# mcu.net
KiCad netlist of a schematic drawn in Altium Designer
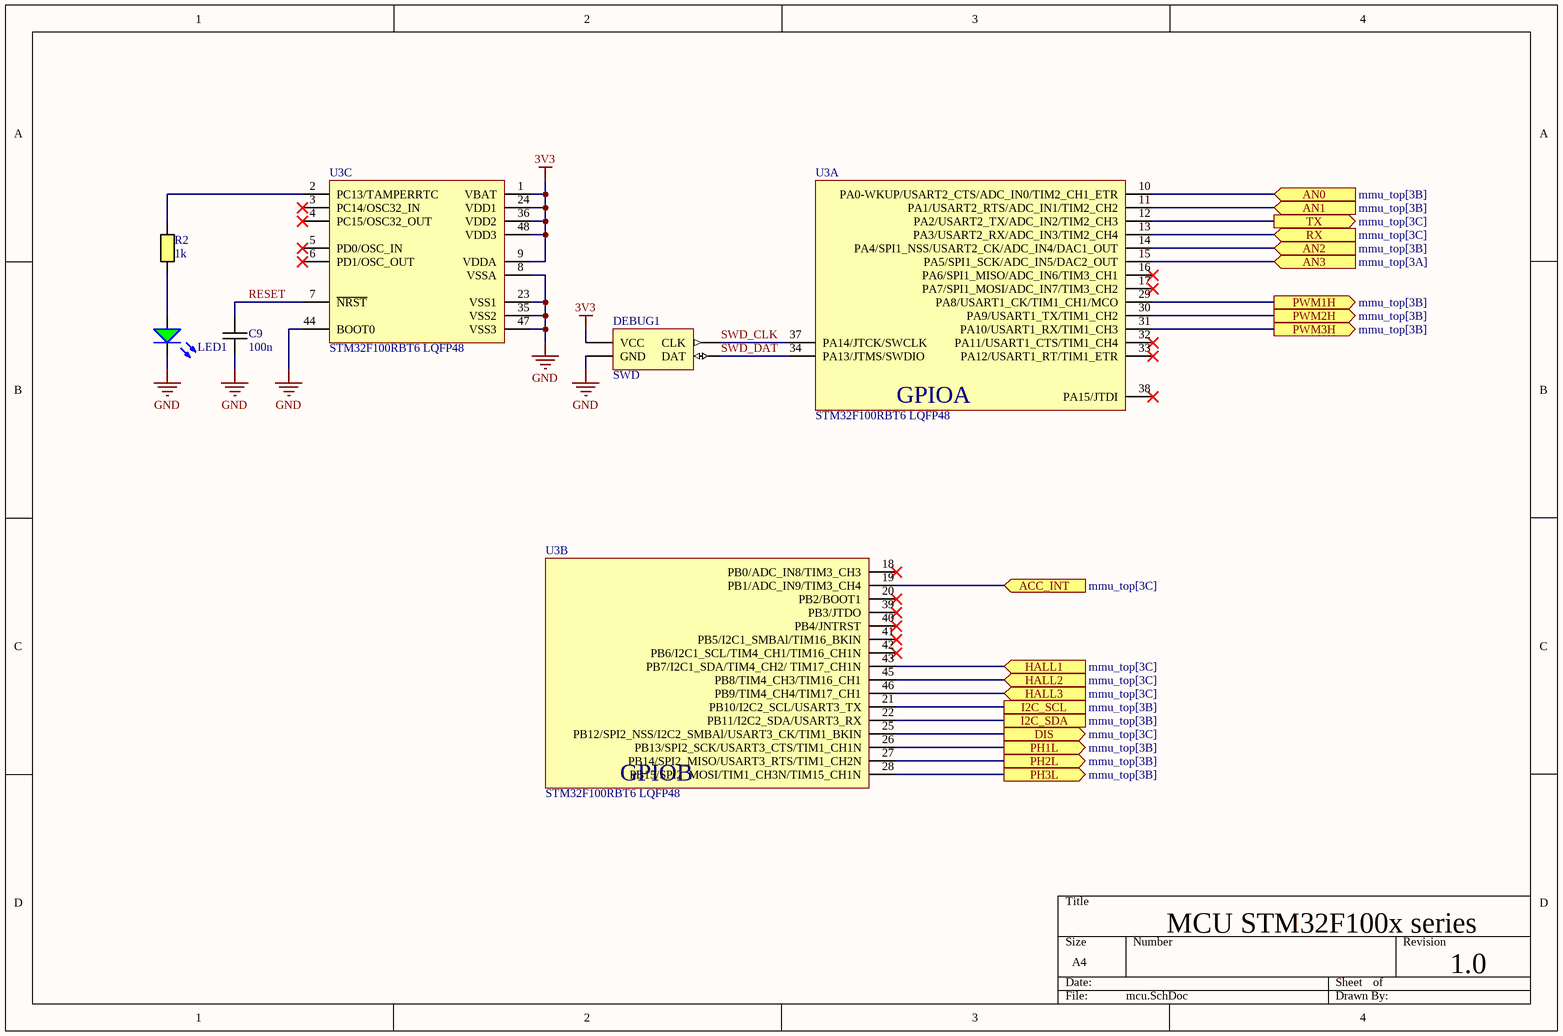
[diagram p0: mcu.SchDoc]

(export (version "E")
  (design (tool "Eeschema 10.0.6"))
  (components
    (comp (ref "C9")
      (value "100n")
      (footprint "CAPC0603(1608)55_N")
      (description "Ceramic capacitor Medium density")
      (libsource (lib "Discrete") (part "Capacitor M"))
    )
    (comp (ref "DEBUG1")
      (value "SWD")
      (footprint "PIN HEADER SINGLE 4")
      (description "SWD ST DEBUG")
      (libsource (lib "Debug") (part "SWD DEBUG"))
    )
    (comp (ref "LED1")
      (value "1206 LED GREEN")
      (footprint "1206 LED GREEN")
      (libsource (lib "Optical") (part "1206 LED GREEN"))
    )
    (comp (ref "R2")
      (value "1k")
      (footprint "RESC0603(1608)_N")
      (description "Resistor Medium Density")
      (libsource (lib "Discrete") (part "Resistor M"))
    )
    (comp (ref "U3")
      (value "STM32F100RBT6 LQFP48")
      (footprint "LQFP48")
      (libsource (lib "Microcontrollers") (part "STM32F100RBT6 LQFP48"))
    )
  )
  (nets
    (net (code "1") (name "/ACC_INT") (class "Default")
      (node (ref "U3") (pin "19") (pinfunction "PB1/ADC_IN9/TIM3_CH4_19") (pintype "passive"))
    )
    (net (code "2") (name "/AN0") (class "Default")
      (node (ref "U3") (pin "10") (pinfunction "PA0-WKUP/USART2_CTS/ADC_IN0/TIM2_CH1_ETR_10") (pintype "passive"))
    )
    (net (code "3") (name "/AN1") (class "Default")
      (node (ref "U3") (pin "11") (pinfunction "PA1/USART2_RTS/ADC_IN1/TIM2_CH2_11") (pintype "passive"))
    )
    (net (code "4") (name "/AN2") (class "Default")
      (node (ref "U3") (pin "14") (pinfunction "PA4/SPI1_NSS/USART2_CK/ADC_IN4/DAC1_OUT_14") (pintype "passive"))
    )
    (net (code "5") (name "/AN3") (class "Default")
      (node (ref "U3") (pin "15") (pinfunction "PA5/SPI1_SCK/ADC_IN5/DAC2_OUT_15") (pintype "passive"))
    )
    (net (code "6") (name "/DIS") (class "Default")
      (node (ref "U3") (pin "25") (pinfunction "PB12/SPI2_NSS/I2C2_SMBAl/USART3_CK/TIM1_BKIN_25") (pintype "passive"))
    )
    (net (code "7") (name "/HALL1") (class "Default")
      (node (ref "U3") (pin "43") (pinfunction "PB7/I2C1_SDA/TIM4_CH2/_TIM17_CH1N_43") (pintype "passive"))
    )
    (net (code "8") (name "/HALL2") (class "Default")
      (node (ref "U3") (pin "45") (pinfunction "PB8/TIM4_CH3/TIM16_CH1_45") (pintype "passive"))
    )
    (net (code "9") (name "/HALL3") (class "Default")
      (node (ref "U3") (pin "46") (pinfunction "PB9/TIM4_CH4/TIM17_CH1_46") (pintype "passive"))
    )
    (net (code "10") (name "/I2C_SCL") (class "Default")
      (node (ref "U3") (pin "21") (pinfunction "PB10/I2C2_SCL/USART3_TX_21") (pintype "passive"))
    )
    (net (code "11") (name "/I2C_SDA") (class "Default")
      (node (ref "U3") (pin "22") (pinfunction "PB11/I2C2_SDA/USART3_RX_22") (pintype "passive"))
    )
    (net (code "12") (name "/PH1L") (class "Default")
      (node (ref "U3") (pin "26") (pinfunction "PB13/SPI2_SCK/USART3_CTS/TIM1_CH1N_26") (pintype "passive"))
    )
    (net (code "13") (name "/PH2L") (class "Default")
      (node (ref "U3") (pin "27") (pinfunction "PB14/SPI2_MISO/USART3_RTS/TIM1_CH2N_27") (pintype "passive"))
    )
    (net (code "14") (name "/PH3L") (class "Default")
      (node (ref "U3") (pin "28") (pinfunction "PB15/SPI2_MOSI/TIM1_CH3N/TIM15_CH1N_28") (pintype "passive"))
    )
    (net (code "15") (name "/PWM1H") (class "Default")
      (node (ref "U3") (pin "29") (pinfunction "PA8/USART1_CK/TIM1_CH1/MCO_29") (pintype "passive"))
    )
    (net (code "16") (name "/PWM2H") (class "Default")
      (node (ref "U3") (pin "30") (pinfunction "PA9/USART1_TX/TIM1_CH2_30") (pintype "passive"))
    )
    (net (code "17") (name "/PWM3H") (class "Default")
      (node (ref "U3") (pin "31") (pinfunction "PA10/USART1_RX/TIM1_CH3_31") (pintype "passive"))
    )
    (net (code "18") (name "/RESET") (class "Default")
      (node (ref "C9") (pin "1") (pinfunction "1_1") (pintype "passive"))
      (node (ref "U3") (pin "7") (pinfunction "~{NRST}_7") (pintype "passive"))
    )
    (net (code "19") (name "/RX") (class "Default")
      (node (ref "U3") (pin "13") (pinfunction "PA3/USART2_RX/ADC_IN3/TIM2_CH4_13") (pintype "passive"))
    )
    (net (code "20") (name "/SWD_CLK") (class "Default")
      (node (ref "DEBUG1") (pin "2") (pinfunction "CLK_2") (pintype "output"))
      (node (ref "U3") (pin "37") (pinfunction "PA14/JTCK/SWCLK_37") (pintype "passive"))
    )
    (net (code "21") (name "/SWD_DAT") (class "Default")
      (node (ref "DEBUG1") (pin "4") (pinfunction "DAT_4") (pintype "bidirectional"))
      (node (ref "U3") (pin "34") (pinfunction "PA13/JTMS/SWDIO_34") (pintype "passive"))
    )
    (net (code "22") (name "/TX") (class "Default")
      (node (ref "U3") (pin "12") (pinfunction "PA2/USART2_TX/ADC_IN2/TIM2_CH3_12") (pintype "passive"))
    )
    (net (code "23") (name "3V3") (class "Default")
      (node (ref "DEBUG1") (pin "1") (pinfunction "VCC_1") (pintype "power_in"))
      (node (ref "U3") (pin "1") (pinfunction "VBAT_1") (pintype "passive"))
      (node (ref "U3") (pin "24") (pinfunction "VDD1_24") (pintype "power_in"))
      (node (ref "U3") (pin "36") (pinfunction "VDD2_36") (pintype "power_in"))
      (node (ref "U3") (pin "48") (pinfunction "VDD3_48") (pintype "power_in"))
      (node (ref "U3") (pin "9") (pinfunction "VDDA_9") (pintype "power_in"))
    )
    (net (code "24") (name "GND") (class "Default")
      (node (ref "C9") (pin "2") (pinfunction "2_2") (pintype "passive"))
      (node (ref "DEBUG1") (pin "3") (pinfunction "GND_3") (pintype "power_in"))
      (node (ref "LED1") (pin "K") (pinfunction "K_K") (pintype "passive"))
      (node (ref "U3") (pin "23") (pinfunction "VSS1_23") (pintype "power_in"))
      (node (ref "U3") (pin "35") (pinfunction "VSS2_35") (pintype "power_in"))
      (node (ref "U3") (pin "44") (pinfunction "BOOT0_44") (pintype "passive"))
      (node (ref "U3") (pin "47") (pinfunction "VSS3_47") (pintype "power_in"))
      (node (ref "U3") (pin "8") (pinfunction "VSSA_8") (pintype "power_in"))
    )
    (net (code "25") (name "Net-(LED1-PadA)") (class "Default")
      (node (ref "LED1") (pin "A") (pinfunction "A_A") (pintype "passive"))
      (node (ref "R2") (pin "1") (pinfunction "1_1") (pintype "passive"))
    )
    (net (code "26") (name "Net-(U3C-PC13{slash}TAMPERRTC)") (class "Default")
      (node (ref "R2") (pin "2") (pinfunction "2_2") (pintype "passive"))
      (node (ref "U3") (pin "2") (pinfunction "PC13/TAMPERRTC_2") (pintype "passive"))
    )
    (net (code "27") (name "unconnected-(U3A-PA6{slash}SPI1_MISO{slash}ADC_IN6{slash}TIM3_CH1-Pad16)") (class "Default")
      (node (ref "U3") (pin "16") (pinfunction "PA6/SPI1_MISO/ADC_IN6/TIM3_CH1_16") (pintype "passive+no_connect"))
    )
    (net (code "28") (name "unconnected-(U3A-PA7{slash}SPI1_MOSI{slash}ADC_IN7{slash}TIM3_CH2-Pad17)") (class "Default")
      (node (ref "U3") (pin "17") (pinfunction "PA7/SPI1_MOSI/ADC_IN7/TIM3_CH2_17") (pintype "passive+no_connect"))
    )
    (net (code "29") (name "unconnected-(U3A-PA11{slash}USART1_CTS{slash}TIM1_CH4-Pad32)") (class "Default")
      (node (ref "U3") (pin "32") (pinfunction "PA11/USART1_CTS/TIM1_CH4_32") (pintype "passive+no_connect"))
    )
    (net (code "30") (name "unconnected-(U3A-PA12{slash}USART1_RT{slash}TIM1_ETR-Pad33)") (class "Default")
      (node (ref "U3") (pin "33") (pinfunction "PA12/USART1_RT/TIM1_ETR_33") (pintype "passive+no_connect"))
    )
    (net (code "31") (name "unconnected-(U3A-PA15{slash}JTDI-Pad38)") (class "Default")
      (node (ref "U3") (pin "38") (pinfunction "PA15/JTDI_38") (pintype "passive+no_connect"))
    )
    (net (code "32") (name "unconnected-(U3B-PB0{slash}ADC_IN8{slash}TIM3_CH3-Pad18)") (class "Default")
      (node (ref "U3") (pin "18") (pinfunction "PB0/ADC_IN8/TIM3_CH3_18") (pintype "passive+no_connect"))
    )
    (net (code "33") (name "unconnected-(U3B-PB2{slash}BOOT1-Pad20)") (class "Default")
      (node (ref "U3") (pin "20") (pinfunction "PB2/BOOT1_20") (pintype "passive+no_connect"))
    )
    (net (code "34") (name "unconnected-(U3B-PB3{slash}JTDO-Pad39)") (class "Default")
      (node (ref "U3") (pin "39") (pinfunction "PB3/JTDO_39") (pintype "passive+no_connect"))
    )
    (net (code "35") (name "unconnected-(U3B-PB4{slash}JNTRST-Pad40)") (class "Default")
      (node (ref "U3") (pin "40") (pinfunction "PB4/JNTRST_40") (pintype "passive+no_connect"))
    )
    (net (code "36") (name "unconnected-(U3B-PB5{slash}I2C1_SMBAl{slash}TIM16_BKIN-Pad41)") (class "Default")
      (node (ref "U3") (pin "41") (pinfunction "PB5/I2C1_SMBAl/TIM16_BKIN_41") (pintype "passive+no_connect"))
    )
    (net (code "37") (name "unconnected-(U3B-PB6{slash}I2C1_SCL{slash}TIM4_CH1{slash}TIM16_CH1N-Pad42)") (class "Default")
      (node (ref "U3") (pin "42") (pinfunction "PB6/I2C1_SCL/TIM4_CH1/TIM16_CH1N_42") (pintype "passive+no_connect"))
    )
    (net (code "38") (name "unconnected-(U3C-PC14{slash}OSC32_IN-Pad3)") (class "Default")
      (node (ref "U3") (pin "3") (pinfunction "PC14/OSC32_IN_3") (pintype "passive+no_connect"))
    )
    (net (code "39") (name "unconnected-(U3C-PC15{slash}OSC32_OUT-Pad4)") (class "Default")
      (node (ref "U3") (pin "4") (pinfunction "PC15/OSC32_OUT_4") (pintype "passive+no_connect"))
    )
    (net (code "40") (name "unconnected-(U3C-PD0{slash}OSC_IN-Pad5)") (class "Default")
      (node (ref "U3") (pin "5") (pinfunction "PD0/OSC_IN_5") (pintype "passive+no_connect"))
    )
    (net (code "41") (name "unconnected-(U3C-PD1{slash}OSC_OUT-Pad6)") (class "Default")
      (node (ref "U3") (pin "6") (pinfunction "PD1/OSC_OUT_6") (pintype "passive+no_connect"))
    )
  )
)
